# COMMUNICATION.net
KiCad netlist of a schematic drawn in Altium Designer
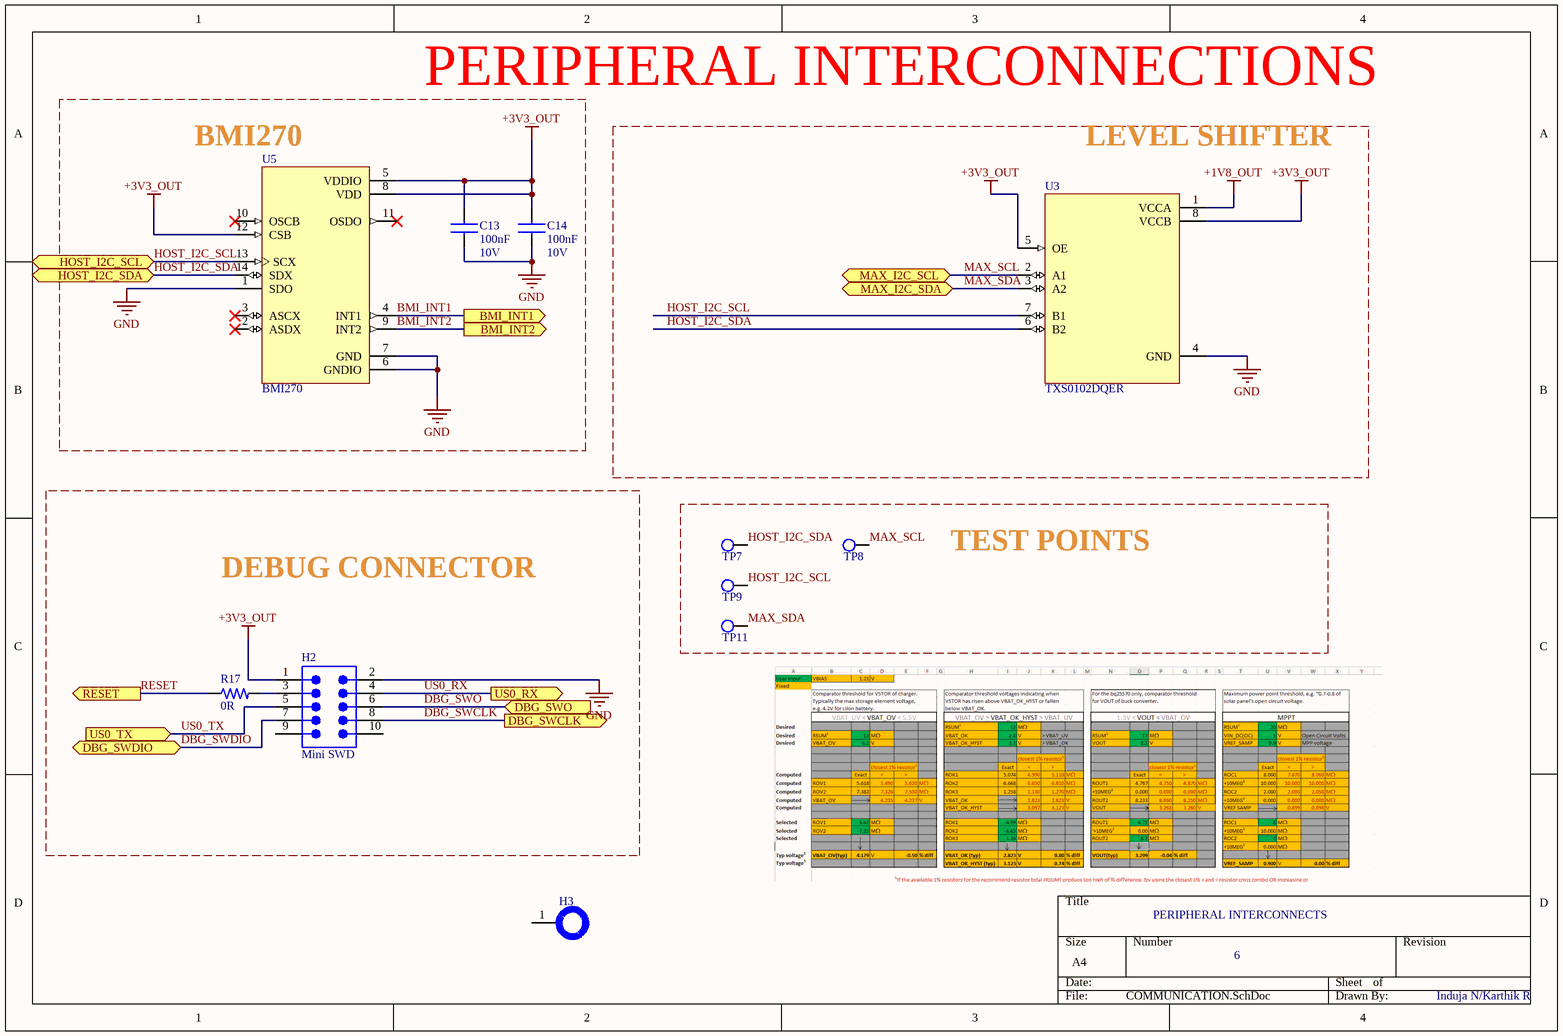
[diagram p0: COMMUNICATION.SchDoc]

(export (version "E")
  (design (tool "Eeschema 10.0.6"))
  (components
    (comp (ref "C13")
      (value "100nF")
      (footprint "CAP_0603_1MM")
      (description "0603 0.1 uF 10 V ±10% Tolerance X7R SMT Multilayer Ceramic Chip Capacitor")
      (fields
        (field (name "MANUFACTURER") "Vishay")
        (field (name "MANUFACTURER PART NUMBER") "VJ0603Y104KXQCW1BC")
        (field (name "VOLTAGE RATING (DC)") "10V")
      )
      (libsource (lib "LPEDT_Components") (part "CAP 0.1uF 0603"))
    )
    (comp (ref "C14")
      (value "100nF")
      (footprint "CAP_0603_1MM")
      (description "0603 0.1 uF 10 V ±10% Tolerance X7R SMT Multilayer Ceramic Chip Capacitor")
      (fields
        (field (name "MANUFACTURER") "Vishay")
        (field (name "MANUFACTURER PART NUMBER") "VJ0603Y104KXQCW1BC")
        (field (name "VOLTAGE RATING (DC)") "10V")
      )
      (libsource (lib "LPEDT_Components") (part "CAP 0.1uF 0603"))
    )
    (comp (ref "H2")
      (value "Mini SWD")
      (footprint "FTSH-105-01-XXX-DV-K")
      (description "Mini SWD 0.05\" Pitch Connector - 10 Pin SMT Box Header")
      (fields
        (field (name "MANUFACTURER") "Adafruit Industries")
        (field (name "MANUFACTURER PART NUMBER") "4048")
      )
      (libsource (lib "LPEDT_Components") (part "Debug Connector Mini SWD - 0.05{dblquote}"))
    )
    (comp (ref "H3")
      (value "~")
      (footprint "PAD Hole")
      (libsource (lib "LPEDT_Components") (part "PAD HOLE"))
    )
    (comp (ref "R17")
      (value "0R")
      (footprint "RES_0603_1608X06")
      (description "GENERAL PURPOSE CHIP RESISTOR Metal Glaze/thick Film, 0.1W, 0ohm, Surface Mount, 0603")
      (fields
        (field (name "MANUFACTURER") "Yageo Group")
        (field (name "MANUFACTURER PART NUMBER") "RC0603JR-070RL")
      )
      (libsource (lib "LPEDT_Components") (part "RES 0R 0603"))
    )
    (comp (ref "TP7")
      (value "Test Point")
      (footprint "Test Point")
      (libsource (lib "LPEDT_Components") (part "Test Point"))
    )
    (comp (ref "TP8")
      (value "Test Point")
      (footprint "Test Point")
      (libsource (lib "LPEDT_Components") (part "Test Point"))
    )
    (comp (ref "TP9")
      (value "Test Point")
      (footprint "Test Point")
      (libsource (lib "LPEDT_Components") (part "Test Point"))
    )
    (comp (ref "TP11")
      (value "Test Point")
      (footprint "Test Point")
      (libsource (lib "LPEDT_Components") (part "Test Point"))
    )
    (comp (ref "U3")
      (value "TXS0102DQER")
      (footprint "SON35P140X100X40-8N")
      (description "2-Bit Bidirectional Voltage-Level Shifter for Open-Drain and Push-Pull Application")
      (fields (field (name "MF") "Texas Instruments"))
      (libsource (lib "LPEDT_Components") (part "TXS0102DQER"))
    )
    (comp (ref "U5")
      (value "BMI270")
      (footprint "XDCR_BMI270")
      (description "Accelerometer, Gyroscope, 6 Axis Sensor IÂ²C, SPI Output")
      (fields (field (name "DIGI-KEY_PART_NUMBER") "828-1091-2-ND") (field (name "MF") "Bosch Sensortec"))
      (libsource (lib "LPEDT_Components") (part "BMI270"))
    )
  )
  (nets
    (net (code "1") (name "+1V8_OUT") (class "Default")
      (node (ref "U3") (pin "1") (pinfunction "VCCA_1") (pintype "power_in"))
    )
    (net (code "2") (name "+3V3_OUT") (class "Default")
      (node (ref "C13") (pin "1") (pinfunction "1_1") (pintype "passive"))
      (node (ref "C14") (pin "1") (pinfunction "1_1") (pintype "passive"))
      (node (ref "H2") (pin "1") (pinfunction "1_1") (pintype "passive"))
      (node (ref "U3") (pin "5") (pinfunction "OE_5") (pintype "input"))
      (node (ref "U3") (pin "8") (pinfunction "VCCB_8") (pintype "power_in"))
      (node (ref "U5") (pin "12") (pinfunction "CSB_12") (pintype "input"))
      (node (ref "U5") (pin "5") (pinfunction "VDDIO_5") (pintype "power_in"))
      (node (ref "U5") (pin "8") (pinfunction "VDD_8") (pintype "power_in"))
    )
    (net (code "3") (name "/BMI_INT1") (class "Default")
      (node (ref "U5") (pin "4") (pinfunction "INT1_4") (pintype "output"))
    )
    (net (code "4") (name "/BMI_INT2") (class "Default")
      (node (ref "U5") (pin "9") (pinfunction "INT2_9") (pintype "output"))
    )
    (net (code "5") (name "/DBG_SWCLK") (class "Default")
      (node (ref "H2") (pin "8") (pinfunction "8_8") (pintype "passive"))
    )
    (net (code "6") (name "/DBG_SWDIO") (class "Default")
      (node (ref "H2") (pin "7") (pinfunction "7_7") (pintype "passive"))
    )
    (net (code "7") (name "/DBG_SWO") (class "Default")
      (node (ref "H2") (pin "6") (pinfunction "6_6") (pintype "passive"))
    )
    (net (code "8") (name "/HOST_I2C_SCL") (class "Default")
      (node (ref "TP9") (pin "1") (pinfunction "1_1") (pintype "passive"))
      (node (ref "U3") (pin "7") (pinfunction "B1_7") (pintype "bidirectional"))
      (node (ref "U5") (pin "13") (pinfunction "SCX_13") (pintype "input"))
    )
    (net (code "9") (name "/HOST_I2C_SDA") (class "Default")
      (node (ref "TP7") (pin "1") (pinfunction "1_1") (pintype "passive"))
      (node (ref "U3") (pin "6") (pinfunction "B2_6") (pintype "bidirectional"))
      (node (ref "U5") (pin "14") (pinfunction "SDX_14") (pintype "bidirectional"))
    )
    (net (code "10") (name "/MAX_SCL") (class "Default")
      (node (ref "TP8") (pin "1") (pinfunction "1_1") (pintype "passive"))
      (node (ref "U3") (pin "2") (pinfunction "A1_2") (pintype "bidirectional"))
    )
    (net (code "11") (name "/MAX_SDA") (class "Default")
      (node (ref "TP11") (pin "1") (pinfunction "1_1") (pintype "passive"))
      (node (ref "U3") (pin "3") (pinfunction "A2_3") (pintype "bidirectional"))
    )
    (net (code "12") (name "/RESET") (class "Default")
      (node (ref "R17") (pin "1") (pinfunction "1_1") (pintype "passive"))
    )
    (net (code "13") (name "/US0_RX") (class "Default")
      (node (ref "H2") (pin "4") (pinfunction "4_4") (pintype "passive"))
    )
    (net (code "14") (name "/US0_TX") (class "Default")
      (node (ref "H2") (pin "5") (pinfunction "5_5") (pintype "passive"))
    )
    (net (code "15") (name "GND") (class "Default")
      (node (ref "C13") (pin "2") (pinfunction "2_2") (pintype "passive"))
      (node (ref "C14") (pin "2") (pinfunction "2_2") (pintype "passive"))
      (node (ref "H2") (pin "2") (pinfunction "2_2") (pintype "passive"))
      (node (ref "U3") (pin "4") (pinfunction "GND_4") (pintype "power_in"))
      (node (ref "U5") (pin "1") (pinfunction "SDO_1") (pintype "passive"))
      (node (ref "U5") (pin "6") (pinfunction "GNDIO_6") (pintype "power_in"))
      (node (ref "U5") (pin "7") (pinfunction "GND_7") (pintype "power_in"))
    )
    (net (code "16") (name "Net-(H2-Pad3)") (class "Default")
      (node (ref "H2") (pin "3") (pinfunction "3_3") (pintype "passive"))
      (node (ref "R17") (pin "2") (pinfunction "2_2") (pintype "passive"))
    )
    (net (code "17") (name "unconnected-(H2-Pad9)") (class "Default")
      (node (ref "H2") (pin "9") (pinfunction "9_9") (pintype "passive"))
    )
    (net (code "18") (name "unconnected-(H2-Pad10)") (class "Default")
      (node (ref "H2") (pin "10") (pinfunction "10_10") (pintype "passive"))
    )
    (net (code "19") (name "unconnected-(H3-Pad1)") (class "Default")
      (node (ref "H3") (pin "1") (pinfunction "1_1") (pintype "passive"))
    )
    (net (code "20") (name "unconnected-(U5-ASCX-Pad3)") (class "Default")
      (node (ref "U5") (pin "3") (pinfunction "ASCX_3") (pintype "bidirectional+no_connect"))
    )
    (net (code "21") (name "unconnected-(U5-ASDX-Pad2)") (class "Default")
      (node (ref "U5") (pin "2") (pinfunction "ASDX_2") (pintype "bidirectional+no_connect"))
    )
    (net (code "22") (name "unconnected-(U5-OSCB-Pad10)") (class "Default")
      (node (ref "U5") (pin "10") (pinfunction "OSCB_10") (pintype "input+no_connect"))
    )
    (net (code "23") (name "unconnected-(U5-OSDO-Pad11)") (class "Default")
      (node (ref "U5") (pin "11") (pinfunction "OSDO_11") (pintype "output+no_connect"))
    )
  )
)
